# 6502_C64_with_m8.net
KiCad netlist of a schematic drawn in EAGLE
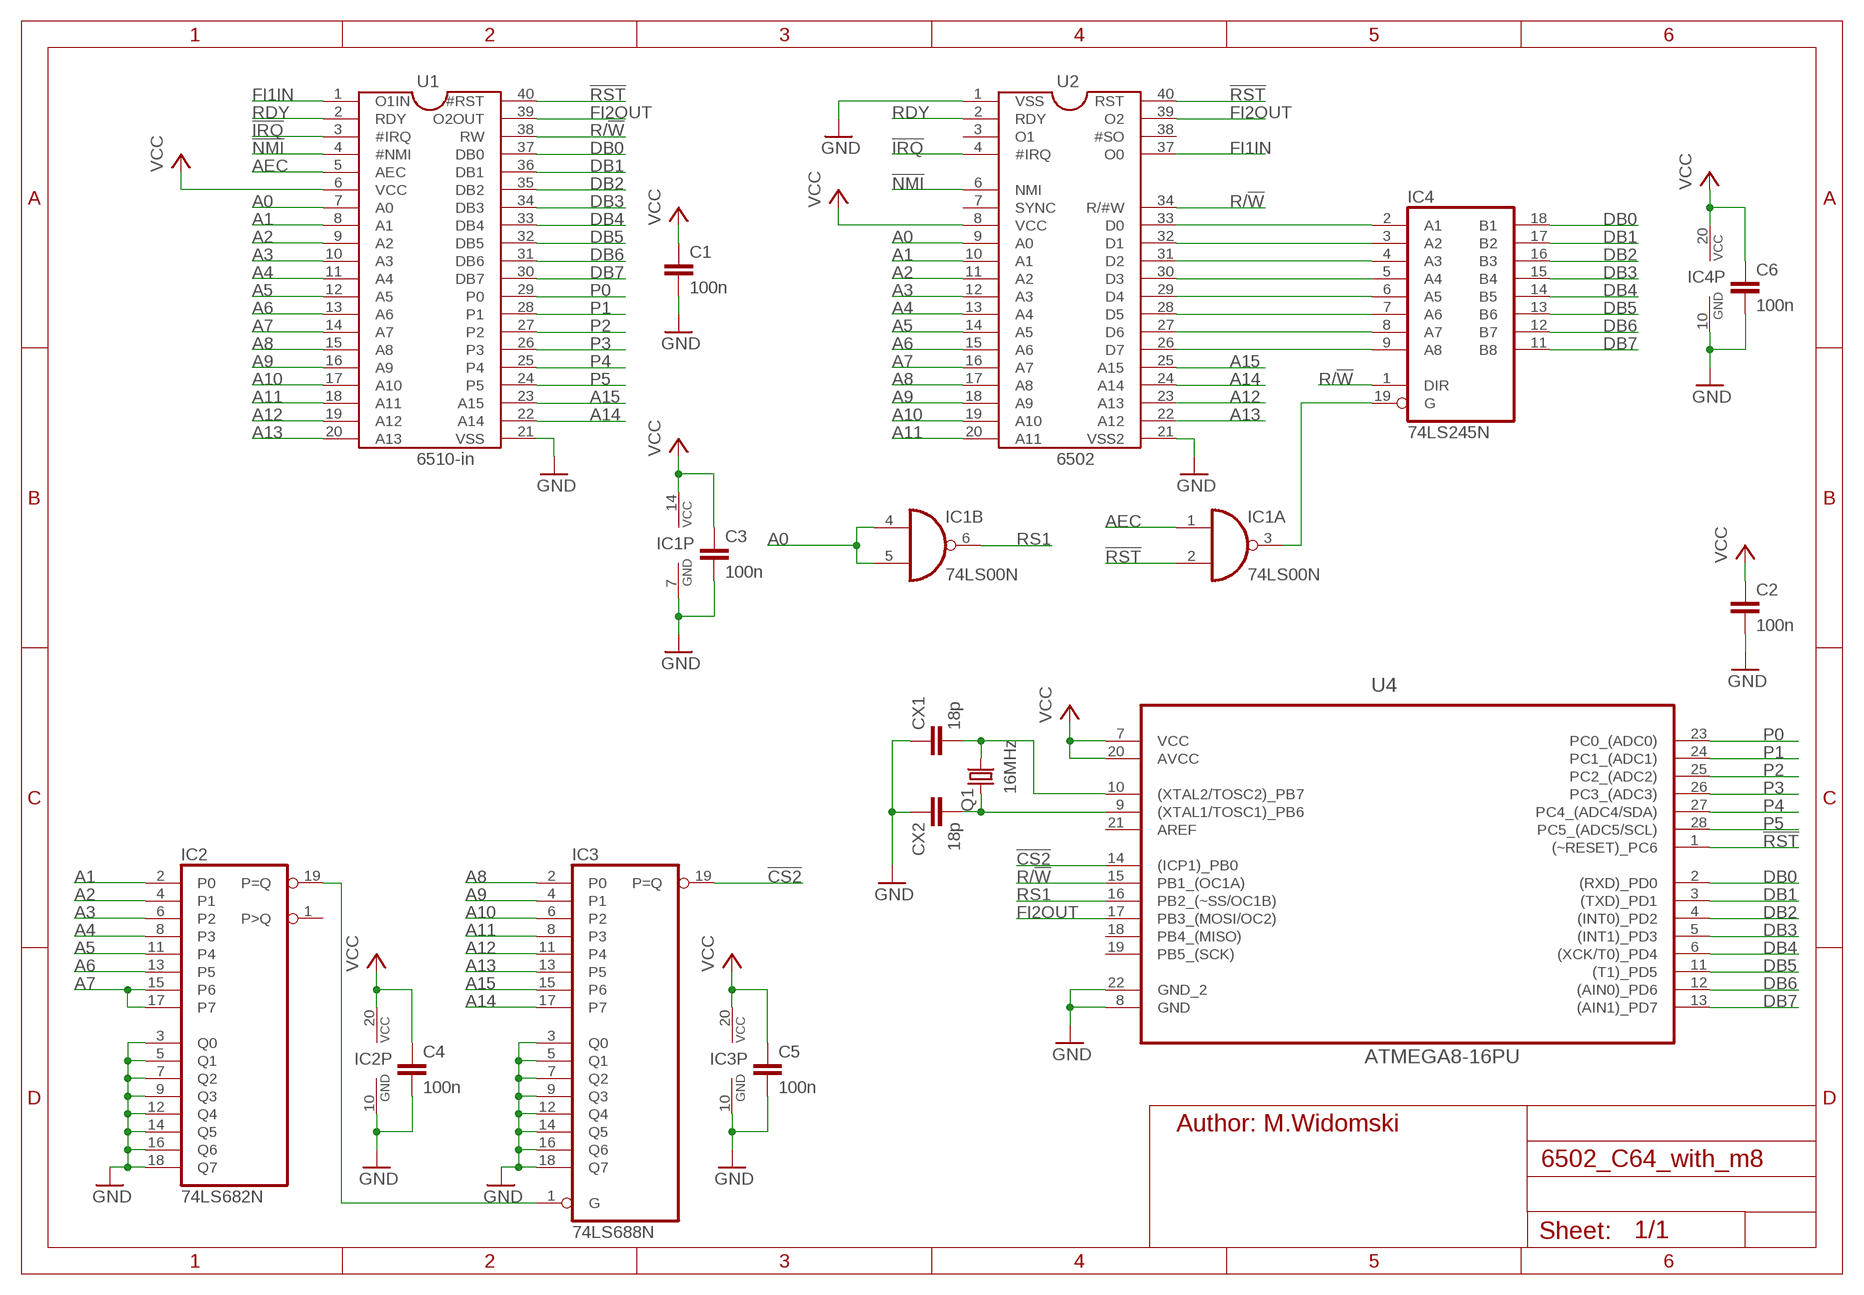
[diagram p0: schematic, sheet 1]

(export (version "E")
  (design (tool "Eeschema 10.0.6"))
  (components
    (comp (ref "C1")
      (value "100n")
      (footprint "eagle-import:C025-025X050")
      (libsource (lib "eagle-import") (part "C-EU025-025X050"))
    )
    (comp (ref "C2")
      (value "100n")
      (footprint "eagle-import:C025-025X050")
      (libsource (lib "eagle-import") (part "C-EU025-025X050"))
    )
    (comp (ref "C3")
      (value "100n")
      (footprint "eagle-import:C025-025X050")
      (libsource (lib "eagle-import") (part "C-EU025-025X050"))
    )
    (comp (ref "C4")
      (value "100n")
      (footprint "eagle-import:C025-025X050")
      (libsource (lib "eagle-import") (part "C-EU025-025X050"))
    )
    (comp (ref "C5")
      (value "100n")
      (footprint "eagle-import:C025-025X050")
      (libsource (lib "eagle-import") (part "C-EU025-025X050"))
    )
    (comp (ref "C6")
      (value "100n")
      (footprint "eagle-import:C025-025X050")
      (libsource (lib "eagle-import") (part "C-EU025-025X050"))
    )
    (comp (ref "CX1")
      (value "18p")
      (footprint "eagle-import:C025-025X050")
      (libsource (lib "eagle-import") (part "C-EU025-025X050"))
    )
    (comp (ref "CX2")
      (value "18p")
      (footprint "eagle-import:C025-025X050")
      (libsource (lib "eagle-import") (part "C-EU025-025X050"))
    )
    (comp (ref "IC1")
      (value "74LS00N")
      (footprint "eagle-import:DIL14")
      (libsource (lib "eagle-import") (part "7400NLS"))
    )
    (comp (ref "IC2")
      (value "74LS682N")
      (footprint "eagle-import:DIL20")
      (libsource (lib "eagle-import") (part "74682NLS"))
    )
    (comp (ref "IC3")
      (value "74LS688N")
      (footprint "eagle-import:DIL20")
      (libsource (lib "eagle-import") (part "74688NLS"))
    )
    (comp (ref "IC4")
      (value "74LS245N")
      (footprint "eagle-import:DIL20")
      (libsource (lib "eagle-import") (part "74245NLS"))
    )
    (comp (ref "Q1")
      (value "16MHz")
      (footprint "eagle-import:HC49_S")
      (libsource (lib "eagle-import") (part "CRYSTALHC49S"))
    )
    (comp (ref "U1")
      (value "6510-in")
      (footprint "eagle-import:DIL40")
      (libsource (lib "eagle-import") (part "6510"))
    )
    (comp (ref "U2")
      (value "6502")
      (footprint "eagle-import:DIL40")
      (libsource (lib "eagle-import") (part "6502"))
    )
    (comp (ref "U4")
      (value "ATMEGA8-16PU")
      (footprint "eagle-import:DIP254P762X457-28")
      (libsource (lib "eagle-import") (part "ATMEGA8-16PU"))
    )
  )
  (nets
    (net (code "1") (name "/A0") (class "Default")
      (node (ref "IC1") (pin "4") (pinfunction "I0_4") (pintype "input"))
      (node (ref "IC1") (pin "5") (pinfunction "I1_5") (pintype "input"))
      (node (ref "U1") (pin "7") (pinfunction "A0_7") (pintype "bidirectional"))
      (node (ref "U2") (pin "9") (pinfunction "A0_9") (pintype "bidirectional"))
    )
    (net (code "2") (name "/A1") (class "Default")
      (node (ref "IC2") (pin "2") (pinfunction "P0_2") (pintype "input"))
      (node (ref "U1") (pin "8") (pinfunction "A1_8") (pintype "bidirectional"))
      (node (ref "U2") (pin "10") (pinfunction "A1_10") (pintype "bidirectional"))
    )
    (net (code "3") (name "/A2") (class "Default")
      (node (ref "IC2") (pin "4") (pinfunction "P1_4") (pintype "input"))
      (node (ref "U1") (pin "9") (pinfunction "A2_9") (pintype "bidirectional"))
      (node (ref "U2") (pin "11") (pinfunction "A2_11") (pintype "bidirectional"))
    )
    (net (code "4") (name "/A3") (class "Default")
      (node (ref "IC2") (pin "6") (pinfunction "P2_6") (pintype "input"))
      (node (ref "U1") (pin "10") (pinfunction "A3_10") (pintype "bidirectional"))
      (node (ref "U2") (pin "12") (pinfunction "A3_12") (pintype "bidirectional"))
    )
    (net (code "5") (name "/A4") (class "Default")
      (node (ref "IC2") (pin "8") (pinfunction "P3_8") (pintype "input"))
      (node (ref "U1") (pin "11") (pinfunction "A4_11") (pintype "bidirectional"))
      (node (ref "U2") (pin "13") (pinfunction "A4_13") (pintype "bidirectional"))
    )
    (net (code "6") (name "/A5") (class "Default")
      (node (ref "IC2") (pin "11") (pinfunction "P4_11") (pintype "input"))
      (node (ref "U1") (pin "12") (pinfunction "A5_12") (pintype "bidirectional"))
      (node (ref "U2") (pin "14") (pinfunction "A5_14") (pintype "bidirectional"))
    )
    (net (code "7") (name "/A6") (class "Default")
      (node (ref "IC2") (pin "13") (pinfunction "P5_13") (pintype "input"))
      (node (ref "U1") (pin "13") (pinfunction "A6_13") (pintype "bidirectional"))
      (node (ref "U2") (pin "15") (pinfunction "A6_15") (pintype "bidirectional"))
    )
    (net (code "8") (name "/A7") (class "Default")
      (node (ref "IC2") (pin "15") (pinfunction "P6_15") (pintype "input"))
      (node (ref "IC2") (pin "17") (pinfunction "P7_17") (pintype "input"))
      (node (ref "U1") (pin "14") (pinfunction "A7_14") (pintype "bidirectional"))
      (node (ref "U2") (pin "16") (pinfunction "A7_16") (pintype "bidirectional"))
    )
    (net (code "9") (name "/A8") (class "Default")
      (node (ref "IC3") (pin "2") (pinfunction "P0_2") (pintype "input"))
      (node (ref "U1") (pin "15") (pinfunction "A8_15") (pintype "bidirectional"))
      (node (ref "U2") (pin "17") (pinfunction "A8_17") (pintype "bidirectional"))
    )
    (net (code "10") (name "/A9") (class "Default")
      (node (ref "IC3") (pin "4") (pinfunction "P1_4") (pintype "input"))
      (node (ref "U1") (pin "16") (pinfunction "A9_16") (pintype "bidirectional"))
      (node (ref "U2") (pin "18") (pinfunction "A9_18") (pintype "bidirectional"))
    )
    (net (code "11") (name "/A10") (class "Default")
      (node (ref "IC3") (pin "6") (pinfunction "P2_6") (pintype "input"))
      (node (ref "U1") (pin "17") (pinfunction "A10_17") (pintype "bidirectional"))
      (node (ref "U2") (pin "19") (pinfunction "A10_19") (pintype "bidirectional"))
    )
    (net (code "12") (name "/A11") (class "Default")
      (node (ref "IC3") (pin "8") (pinfunction "P3_8") (pintype "input"))
      (node (ref "U1") (pin "18") (pinfunction "A11_18") (pintype "bidirectional"))
      (node (ref "U2") (pin "20") (pinfunction "A11_20") (pintype "bidirectional"))
    )
    (net (code "13") (name "/A12") (class "Default")
      (node (ref "IC3") (pin "11") (pinfunction "P4_11") (pintype "input"))
      (node (ref "U1") (pin "19") (pinfunction "A12_19") (pintype "bidirectional"))
      (node (ref "U2") (pin "23") (pinfunction "A13_23") (pintype "bidirectional"))
    )
    (net (code "14") (name "/A13") (class "Default")
      (node (ref "IC3") (pin "13") (pinfunction "P5_13") (pintype "input"))
      (node (ref "U1") (pin "20") (pinfunction "A13_20") (pintype "bidirectional"))
      (node (ref "U2") (pin "22") (pinfunction "A12_22") (pintype "bidirectional"))
    )
    (net (code "15") (name "/A14") (class "Default")
      (node (ref "IC3") (pin "17") (pinfunction "P7_17") (pintype "input"))
      (node (ref "U1") (pin "22") (pinfunction "A14_22") (pintype "bidirectional"))
      (node (ref "U2") (pin "24") (pinfunction "A14_24") (pintype "bidirectional"))
    )
    (net (code "16") (name "/A15") (class "Default")
      (node (ref "IC3") (pin "15") (pinfunction "P6_15") (pintype "input"))
      (node (ref "U1") (pin "23") (pinfunction "A15_23") (pintype "bidirectional"))
      (node (ref "U2") (pin "25") (pinfunction "A15_25") (pintype "bidirectional"))
    )
    (net (code "17") (name "/AEC") (class "Default")
      (node (ref "IC1") (pin "1") (pinfunction "I0_1") (pintype "input"))
      (node (ref "U1") (pin "5") (pinfunction "AEC_5") (pintype "bidirectional"))
    )
    (net (code "18") (name "/DB0") (class "Default")
      (node (ref "IC4") (pin "18") (pinfunction "B1_18") (pintype "bidirectional"))
      (node (ref "U1") (pin "37") (pinfunction "DB0_37") (pintype "bidirectional"))
      (node (ref "U4") (pin "2") (pinfunction "(RXD)_PD0_2") (pintype "bidirectional"))
    )
    (net (code "19") (name "/DB1") (class "Default")
      (node (ref "IC4") (pin "17") (pinfunction "B2_17") (pintype "bidirectional"))
      (node (ref "U1") (pin "36") (pinfunction "DB1_36") (pintype "bidirectional"))
      (node (ref "U4") (pin "3") (pinfunction "(TXD)_PD1_3") (pintype "bidirectional"))
    )
    (net (code "20") (name "/DB2") (class "Default")
      (node (ref "IC4") (pin "16") (pinfunction "B3_16") (pintype "bidirectional"))
      (node (ref "U1") (pin "35") (pinfunction "DB2_35") (pintype "bidirectional"))
      (node (ref "U4") (pin "4") (pinfunction "(INT0)_PD2_4") (pintype "bidirectional"))
    )
    (net (code "21") (name "/DB3") (class "Default")
      (node (ref "IC4") (pin "15") (pinfunction "B4_15") (pintype "bidirectional"))
      (node (ref "U1") (pin "34") (pinfunction "DB3_34") (pintype "bidirectional"))
      (node (ref "U4") (pin "5") (pinfunction "(INT1)_PD3_5") (pintype "bidirectional"))
    )
    (net (code "22") (name "/DB4") (class "Default")
      (node (ref "IC4") (pin "14") (pinfunction "B5_14") (pintype "bidirectional"))
      (node (ref "U1") (pin "33") (pinfunction "DB4_33") (pintype "bidirectional"))
      (node (ref "U4") (pin "6") (pinfunction "(XCK/T0)_PD4_6") (pintype "bidirectional"))
    )
    (net (code "23") (name "/DB5") (class "Default")
      (node (ref "IC4") (pin "13") (pinfunction "B6_13") (pintype "bidirectional"))
      (node (ref "U1") (pin "32") (pinfunction "DB5_32") (pintype "bidirectional"))
      (node (ref "U4") (pin "11") (pinfunction "(T1)_PD5_11") (pintype "bidirectional"))
    )
    (net (code "24") (name "/DB6") (class "Default")
      (node (ref "IC4") (pin "12") (pinfunction "B7_12") (pintype "bidirectional"))
      (node (ref "U1") (pin "31") (pinfunction "DB6_31") (pintype "bidirectional"))
      (node (ref "U4") (pin "12") (pinfunction "(AIN0)_PD6_12") (pintype "bidirectional"))
    )
    (net (code "25") (name "/DB7") (class "Default")
      (node (ref "IC4") (pin "11") (pinfunction "B8_11") (pintype "bidirectional"))
      (node (ref "U1") (pin "30") (pinfunction "DB7_30") (pintype "bidirectional"))
      (node (ref "U4") (pin "13") (pinfunction "(AIN1)_PD7_13") (pintype "bidirectional"))
    )
    (net (code "26") (name "/FI1IN") (class "Default")
      (node (ref "U1") (pin "1") (pinfunction "O1IN_1") (pintype "bidirectional"))
      (node (ref "U2") (pin "37") (pinfunction "O0_37") (pintype "bidirectional"))
    )
    (net (code "27") (name "/FI2OUT") (class "Default")
      (node (ref "U1") (pin "39") (pinfunction "O2OUT_39") (pintype "bidirectional"))
      (node (ref "U2") (pin "39") (pinfunction "O2_39") (pintype "bidirectional"))
      (node (ref "U4") (pin "17") (pinfunction "PB3_(MOSI/OC2)_17") (pintype "bidirectional"))
    )
    (net (code "28") (name "/P0") (class "Default")
      (node (ref "U1") (pin "29") (pinfunction "P0_29") (pintype "bidirectional"))
      (node (ref "U4") (pin "23") (pinfunction "PC0_(ADC0)_23") (pintype "bidirectional"))
    )
    (net (code "29") (name "/P1") (class "Default")
      (node (ref "U1") (pin "28") (pinfunction "P1_28") (pintype "bidirectional"))
      (node (ref "U4") (pin "24") (pinfunction "PC1_(ADC1)_24") (pintype "bidirectional"))
    )
    (net (code "30") (name "/P2") (class "Default")
      (node (ref "U1") (pin "27") (pinfunction "P2_27") (pintype "bidirectional"))
      (node (ref "U4") (pin "25") (pinfunction "PC2_(ADC2)_25") (pintype "bidirectional"))
    )
    (net (code "31") (name "/P3") (class "Default")
      (node (ref "U1") (pin "26") (pinfunction "P3_26") (pintype "bidirectional"))
      (node (ref "U4") (pin "26") (pinfunction "PC3_(ADC3)_26") (pintype "bidirectional"))
    )
    (net (code "32") (name "/P4") (class "Default")
      (node (ref "U1") (pin "25") (pinfunction "P4_25") (pintype "bidirectional"))
      (node (ref "U4") (pin "27") (pinfunction "PC4_(ADC4/SDA)_27") (pintype "bidirectional"))
    )
    (net (code "33") (name "/P5") (class "Default")
      (node (ref "U1") (pin "24") (pinfunction "P5_24") (pintype "bidirectional"))
      (node (ref "U4") (pin "28") (pinfunction "PC5_(ADC5/SCL)_28") (pintype "bidirectional"))
    )
    (net (code "34") (name "/RDY") (class "Default")
      (node (ref "U1") (pin "2") (pinfunction "RDY_2") (pintype "bidirectional"))
      (node (ref "U2") (pin "2") (pinfunction "RDY_2") (pintype "bidirectional"))
    )
    (net (code "35") (name "/RS1") (class "Default")
      (node (ref "IC1") (pin "6") (pinfunction "O_6") (pintype "output"))
      (node (ref "U4") (pin "16") (pinfunction "PB2_(~{SS/OC1B})_16") (pintype "bidirectional"))
    )
    (net (code "36") (name "/R{slash}~{W}") (class "Default")
      (node (ref "IC4") (pin "1") (pinfunction "DIR_1") (pintype "input"))
      (node (ref "U1") (pin "38") (pinfunction "RW_38") (pintype "bidirectional"))
      (node (ref "U2") (pin "34") (pinfunction "R/#W_34") (pintype "bidirectional"))
      (node (ref "U4") (pin "15") (pinfunction "PB1_(OC1A)_15") (pintype "bidirectional"))
    )
    (net (code "37") (name "/~{CS2}") (class "Default")
      (node (ref "IC3") (pin "19") (pinfunction "P=Q_19") (pintype "output"))
      (node (ref "U4") (pin "14") (pinfunction "(ICP1)_PB0_14") (pintype "bidirectional"))
    )
    (net (code "38") (name "/~{IRQ}") (class "Default")
      (node (ref "U1") (pin "3") (pinfunction "#IRQ_3") (pintype "bidirectional"))
      (node (ref "U2") (pin "4") (pinfunction "#IRQ_4") (pintype "bidirectional"))
    )
    (net (code "39") (name "/~{NMI}") (class "Default")
      (node (ref "U1") (pin "4") (pinfunction "#NMI_4") (pintype "bidirectional"))
      (node (ref "U2") (pin "6") (pinfunction "NMI_6") (pintype "bidirectional"))
    )
    (net (code "40") (name "/~{RST}") (class "Default")
      (node (ref "IC1") (pin "2") (pinfunction "I1_2") (pintype "input"))
      (node (ref "U1") (pin "40") (pinfunction "#RST_40") (pintype "bidirectional"))
      (node (ref "U2") (pin "40") (pinfunction "RST_40") (pintype "bidirectional"))
      (node (ref "U4") (pin "1") (pinfunction "(~{RESET})_PC6_1") (pintype "bidirectional"))
    )
    (net (code "41") (name "GND") (class "Default")
      (node (ref "C1") (pin "2") (pinfunction "2_2") (pintype "passive"))
      (node (ref "C2") (pin "2") (pinfunction "2_2") (pintype "passive"))
      (node (ref "C3") (pin "2") (pinfunction "2_2") (pintype "passive"))
      (node (ref "C4") (pin "2") (pinfunction "2_2") (pintype "passive"))
      (node (ref "C5") (pin "2") (pinfunction "2_2") (pintype "passive"))
      (node (ref "C6") (pin "2") (pinfunction "2_2") (pintype "passive"))
      (node (ref "CX1") (pin "1") (pinfunction "1_1") (pintype "passive"))
      (node (ref "CX2") (pin "2") (pinfunction "2_2") (pintype "passive"))
      (node (ref "IC1") (pin "7") (pinfunction "GND_7") (pintype "power_in"))
      (node (ref "IC2") (pin "10") (pinfunction "GND_10") (pintype "power_in"))
      (node (ref "IC2") (pin "12") (pinfunction "Q4_12") (pintype "input"))
      (node (ref "IC2") (pin "14") (pinfunction "Q5_14") (pintype "input"))
      (node (ref "IC2") (pin "16") (pinfunction "Q6_16") (pintype "input"))
      (node (ref "IC2") (pin "18") (pinfunction "Q7_18") (pintype "input"))
      (node (ref "IC2") (pin "3") (pinfunction "Q0_3") (pintype "input"))
      (node (ref "IC2") (pin "5") (pinfunction "Q1_5") (pintype "input"))
      (node (ref "IC2") (pin "7") (pinfunction "Q2_7") (pintype "input"))
      (node (ref "IC2") (pin "9") (pinfunction "Q3_9") (pintype "input"))
      (node (ref "IC3") (pin "10") (pinfunction "GND_10") (pintype "power_in"))
      (node (ref "IC3") (pin "12") (pinfunction "Q4_12") (pintype "input"))
      (node (ref "IC3") (pin "14") (pinfunction "Q5_14") (pintype "input"))
      (node (ref "IC3") (pin "16") (pinfunction "Q6_16") (pintype "input"))
      (node (ref "IC3") (pin "18") (pinfunction "Q7_18") (pintype "input"))
      (node (ref "IC3") (pin "3") (pinfunction "Q0_3") (pintype "input"))
      (node (ref "IC3") (pin "5") (pinfunction "Q1_5") (pintype "input"))
      (node (ref "IC3") (pin "7") (pinfunction "Q2_7") (pintype "input"))
      (node (ref "IC3") (pin "9") (pinfunction "Q3_9") (pintype "input"))
      (node (ref "IC4") (pin "10") (pinfunction "GND_10") (pintype "power_in"))
      (node (ref "U1") (pin "21") (pinfunction "VSS_21") (pintype "bidirectional"))
      (node (ref "U2") (pin "1") (pinfunction "VSS_1") (pintype "bidirectional"))
      (node (ref "U2") (pin "21") (pinfunction "VSS2_21") (pintype "bidirectional"))
      (node (ref "U4") (pin "22") (pinfunction "GND_2_22") (pintype "passive"))
      (node (ref "U4") (pin "8") (pinfunction "GND_8") (pintype "passive"))
    )
    (net (code "42") (name "Net-(IC1A-O)") (class "Default")
      (node (ref "IC1") (pin "3") (pinfunction "O_3") (pintype "output"))
      (node (ref "IC4") (pin "19") (pinfunction "G_19") (pintype "input"))
    )
    (net (code "43") (name "Net-(IC2A-P=Q)") (class "Default")
      (node (ref "IC2") (pin "19") (pinfunction "P=Q_19") (pintype "output"))
      (node (ref "IC3") (pin "1") (pinfunction "G_1") (pintype "input"))
    )
    (net (code "44") (name "Net-(IC4A-A1)") (class "Default")
      (node (ref "IC4") (pin "2") (pinfunction "A1_2") (pintype "bidirectional"))
      (node (ref "U2") (pin "33") (pinfunction "D0_33") (pintype "bidirectional"))
    )
    (net (code "45") (name "Net-(IC4A-A2)") (class "Default")
      (node (ref "IC4") (pin "3") (pinfunction "A2_3") (pintype "bidirectional"))
      (node (ref "U2") (pin "32") (pinfunction "D1_32") (pintype "bidirectional"))
    )
    (net (code "46") (name "Net-(IC4A-A3)") (class "Default")
      (node (ref "IC4") (pin "4") (pinfunction "A3_4") (pintype "bidirectional"))
      (node (ref "U2") (pin "31") (pinfunction "D2_31") (pintype "bidirectional"))
    )
    (net (code "47") (name "Net-(IC4A-A4)") (class "Default")
      (node (ref "IC4") (pin "5") (pinfunction "A4_5") (pintype "bidirectional"))
      (node (ref "U2") (pin "30") (pinfunction "D3_30") (pintype "bidirectional"))
    )
    (net (code "48") (name "Net-(IC4A-A5)") (class "Default")
      (node (ref "IC4") (pin "6") (pinfunction "A5_6") (pintype "bidirectional"))
      (node (ref "U2") (pin "29") (pinfunction "D4_29") (pintype "bidirectional"))
    )
    (net (code "49") (name "Net-(IC4A-A6)") (class "Default")
      (node (ref "IC4") (pin "7") (pinfunction "A6_7") (pintype "bidirectional"))
      (node (ref "U2") (pin "28") (pinfunction "D5_28") (pintype "bidirectional"))
    )
    (net (code "50") (name "Net-(IC4A-A7)") (class "Default")
      (node (ref "IC4") (pin "8") (pinfunction "A7_8") (pintype "bidirectional"))
      (node (ref "U2") (pin "27") (pinfunction "D6_27") (pintype "bidirectional"))
    )
    (net (code "51") (name "Net-(IC4A-A8)") (class "Default")
      (node (ref "IC4") (pin "9") (pinfunction "A8_9") (pintype "bidirectional"))
      (node (ref "U2") (pin "26") (pinfunction "D7_26") (pintype "bidirectional"))
    )
    (net (code "52") (name "Net-(U4-(XTAL1{slash}TOSC1)_PB6)") (class "Default")
      (node (ref "CX2") (pin "1") (pinfunction "1_1") (pintype "passive"))
      (node (ref "Q1") (pin "1") (pinfunction "1_1") (pintype "passive"))
      (node (ref "U4") (pin "9") (pinfunction "(XTAL1/TOSC1)_PB6_9") (pintype "input"))
    )
    (net (code "53") (name "Net-(U4-(XTAL2{slash}TOSC2)_PB7)") (class "Default")
      (node (ref "CX1") (pin "2") (pinfunction "2_2") (pintype "passive"))
      (node (ref "Q1") (pin "2") (pinfunction "2_2") (pintype "passive"))
      (node (ref "U4") (pin "10") (pinfunction "(XTAL2/TOSC2)_PB7_10") (pintype "input"))
    )
    (net (code "54") (name "VCC") (class "Default")
      (node (ref "C1") (pin "1") (pinfunction "1_1") (pintype "passive"))
      (node (ref "C2") (pin "1") (pinfunction "1_1") (pintype "passive"))
      (node (ref "C3") (pin "1") (pinfunction "1_1") (pintype "passive"))
      (node (ref "C4") (pin "1") (pinfunction "1_1") (pintype "passive"))
      (node (ref "C5") (pin "1") (pinfunction "1_1") (pintype "passive"))
      (node (ref "C6") (pin "1") (pinfunction "1_1") (pintype "passive"))
      (node (ref "IC1") (pin "14") (pinfunction "VCC_14") (pintype "power_in"))
      (node (ref "IC2") (pin "20") (pinfunction "VCC_20") (pintype "power_in"))
      (node (ref "IC3") (pin "20") (pinfunction "VCC_20") (pintype "power_in"))
      (node (ref "IC4") (pin "20") (pinfunction "VCC_20") (pintype "power_in"))
      (node (ref "U1") (pin "6") (pinfunction "VCC_6") (pintype "bidirectional"))
      (node (ref "U2") (pin "8") (pinfunction "VCC_8") (pintype "bidirectional"))
      (node (ref "U4") (pin "20") (pinfunction "AVCC_20") (pintype "power_in"))
      (node (ref "U4") (pin "7") (pinfunction "VCC_7") (pintype "power_in"))
    )
    (net (code "55") (name "unconnected-(IC2A-P>Q-Pad1)") (class "Default")
      (node (ref "IC2") (pin "1") (pinfunction "P>Q_1") (pintype "output"))
    )
    (net (code "56") (name "unconnected-(U2-#SO-Pad38)") (class "Default")
      (node (ref "U2") (pin "38") (pinfunction "#SO_38") (pintype "bidirectional"))
    )
    (net (code "57") (name "unconnected-(U2-O1-Pad3)") (class "Default")
      (node (ref "U2") (pin "3") (pinfunction "O1_3") (pintype "bidirectional"))
    )
    (net (code "58") (name "unconnected-(U2-SYNC-Pad7)") (class "Default")
      (node (ref "U2") (pin "7") (pinfunction "SYNC_7") (pintype "bidirectional"))
    )
    (net (code "59") (name "unconnected-(U4-AREF-Pad21)") (class "Default")
      (node (ref "U4") (pin "21") (pinfunction "AREF_21") (pintype "input"))
    )
    (net (code "60") (name "unconnected-(U4-PB4_(MISO)-Pad18)") (class "Default")
      (node (ref "U4") (pin "18") (pinfunction "PB4_(MISO)_18") (pintype "bidirectional"))
    )
    (net (code "61") (name "unconnected-(U4-PB5_(SCK)-Pad19)") (class "Default")
      (node (ref "U4") (pin "19") (pinfunction "PB5_(SCK)_19") (pintype "bidirectional"))
    )
  )
)
